# hiral_pcb.net
KiCad netlist of a schematic drawn in EAGLE
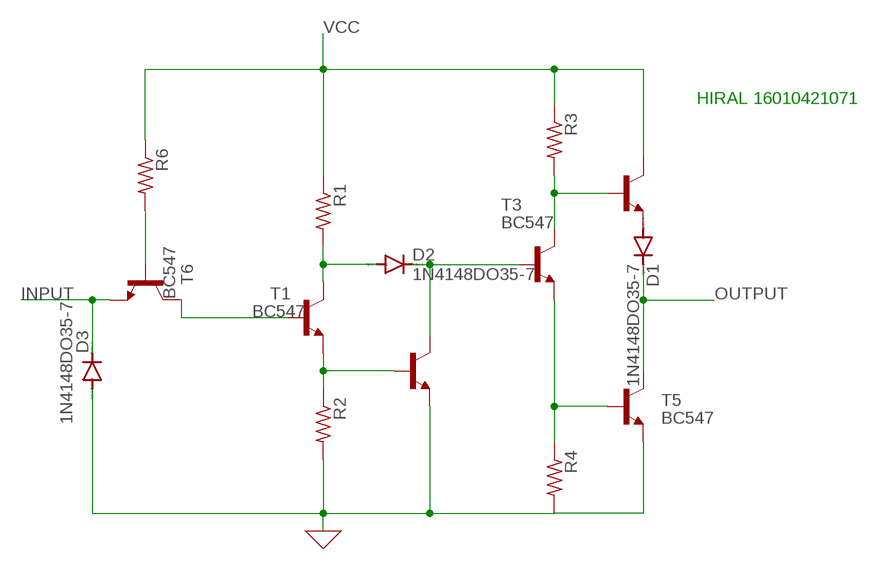
[diagram p0: schematic, sheet 1]

(export (version "E")
  (design (tool "Eeschema 10.0.6"))
  (components
    (comp (ref "D1")
      (value "1N4148DO35-7")
      (footprint "eagle-import:DO35-7")
      (libsource (lib "eagle-import") (part "1N4148DO35-7"))
    )
    (comp (ref "D2")
      (value "1N4148DO35-7")
      (footprint "eagle-import:DO35-7")
      (libsource (lib "eagle-import") (part "1N4148DO35-7"))
    )
    (comp (ref "D3")
      (value "1N4148DO35-7")
      (footprint "eagle-import:DO35-7")
      (libsource (lib "eagle-import") (part "1N4148DO35-7"))
    )
    (comp (ref "R1")
      (value "R-US_0204/5")
      (footprint "eagle-import:0204_5")
      (libsource (lib "eagle-import") (part "R-US_0204/5"))
    )
    (comp (ref "R2")
      (value "R-US_0204/5")
      (footprint "eagle-import:0204_5")
      (libsource (lib "eagle-import") (part "R-US_0204/5"))
    )
    (comp (ref "R3")
      (value "R-US_0204/5")
      (footprint "eagle-import:0204_5")
      (libsource (lib "eagle-import") (part "R-US_0204/5"))
    )
    (comp (ref "R4")
      (value "R-US_0204/5")
      (footprint "eagle-import:0204_5")
      (libsource (lib "eagle-import") (part "R-US_0204/5"))
    )
    (comp (ref "R6")
      (value "R-US_0204/5")
      (footprint "eagle-import:0204_5")
      (libsource (lib "eagle-import") (part "R-US_0204/5"))
    )
    (comp (ref "T1")
      (value "BC547")
      (footprint "eagle-import:TO92")
      (libsource (lib "eagle-import") (part "BC547"))
    )
    (comp (ref "T2")
      (value "BC547")
      (footprint "eagle-import:TO92")
      (libsource (lib "eagle-import") (part "BC547"))
    )
    (comp (ref "T3")
      (value "BC547")
      (footprint "eagle-import:TO92")
      (libsource (lib "eagle-import") (part "BC547"))
    )
    (comp (ref "T4")
      (value "BC547")
      (footprint "eagle-import:TO92")
      (libsource (lib "eagle-import") (part "BC547"))
    )
    (comp (ref "T5")
      (value "BC547")
      (footprint "eagle-import:TO92")
      (libsource (lib "eagle-import") (part "BC547"))
    )
    (comp (ref "T6")
      (value "BC547")
      (footprint "eagle-import:TO92")
      (libsource (lib "eagle-import") (part "BC547"))
    )
  )
  (nets
    (net (code "1") (name "/INPUT") (class "Default")
      (node (ref "D3") (pin "C") (pinfunction "C_C") (pintype "passive"))
      (node (ref "T6") (pin "1") (pinfunction "E_1") (pintype "passive"))
    )
    (net (code "2") (name "/OUTPUT") (class "Default")
      (node (ref "D1") (pin "C") (pinfunction "C_C") (pintype "passive"))
      (node (ref "T5") (pin "3") (pinfunction "C_3") (pintype "passive"))
    )
    (net (code "3") (name "/VCC") (class "Default")
      (node (ref "R1") (pin "1") (pinfunction "1_1") (pintype "passive"))
      (node (ref "R3") (pin "1") (pinfunction "1_1") (pintype "passive"))
      (node (ref "R6") (pin "1") (pinfunction "1_1") (pintype "passive"))
      (node (ref "T4") (pin "3") (pinfunction "C_3") (pintype "passive"))
    )
    (net (code "4") (name "GND") (class "Default")
      (node (ref "D3") (pin "A") (pinfunction "A_A") (pintype "passive"))
      (node (ref "R2") (pin "2") (pinfunction "2_2") (pintype "passive"))
      (node (ref "R4") (pin "2") (pinfunction "2_2") (pintype "passive"))
      (node (ref "T2") (pin "1") (pinfunction "E_1") (pintype "passive"))
      (node (ref "T5") (pin "1") (pinfunction "E_1") (pintype "passive"))
    )
    (net (code "5") (name "Net-(T1-B)") (class "Default")
      (node (ref "T1") (pin "2") (pinfunction "B_2") (pintype "passive"))
      (node (ref "T6") (pin "3") (pinfunction "C_3") (pintype "passive"))
    )
    (net (code "6") (name "Net-(T1-C)") (class "Default")
      (node (ref "D2") (pin "A") (pinfunction "A_A") (pintype "passive"))
      (node (ref "R1") (pin "2") (pinfunction "2_2") (pintype "passive"))
      (node (ref "T1") (pin "3") (pinfunction "C_3") (pintype "passive"))
    )
    (net (code "7") (name "Net-(T1-E)") (class "Default")
      (node (ref "R2") (pin "1") (pinfunction "1_1") (pintype "passive"))
      (node (ref "T1") (pin "1") (pinfunction "E_1") (pintype "passive"))
      (node (ref "T2") (pin "2") (pinfunction "B_2") (pintype "passive"))
    )
    (net (code "8") (name "Net-(T2-C)") (class "Default")
      (node (ref "D2") (pin "C") (pinfunction "C_C") (pintype "passive"))
      (node (ref "T2") (pin "3") (pinfunction "C_3") (pintype "passive"))
      (node (ref "T3") (pin "2") (pinfunction "B_2") (pintype "passive"))
    )
    (net (code "9") (name "Net-(T3-C)") (class "Default")
      (node (ref "R3") (pin "2") (pinfunction "2_2") (pintype "passive"))
      (node (ref "T3") (pin "3") (pinfunction "C_3") (pintype "passive"))
      (node (ref "T4") (pin "2") (pinfunction "B_2") (pintype "passive"))
    )
    (net (code "10") (name "Net-(T3-E)") (class "Default")
      (node (ref "R4") (pin "1") (pinfunction "1_1") (pintype "passive"))
      (node (ref "T3") (pin "1") (pinfunction "E_1") (pintype "passive"))
      (node (ref "T5") (pin "2") (pinfunction "B_2") (pintype "passive"))
    )
    (net (code "11") (name "Net-(T4-E)") (class "Default")
      (node (ref "D1") (pin "A") (pinfunction "A_A") (pintype "passive"))
      (node (ref "T4") (pin "1") (pinfunction "E_1") (pintype "passive"))
    )
    (net (code "12") (name "Net-(T6-B)") (class "Default")
      (node (ref "R6") (pin "2") (pinfunction "2_2") (pintype "passive"))
      (node (ref "T6") (pin "2") (pinfunction "B_2") (pintype "passive"))
    )
  )
)
